# internal_excitation_2.net
KiCad netlist of a schematic drawn in EAGLE
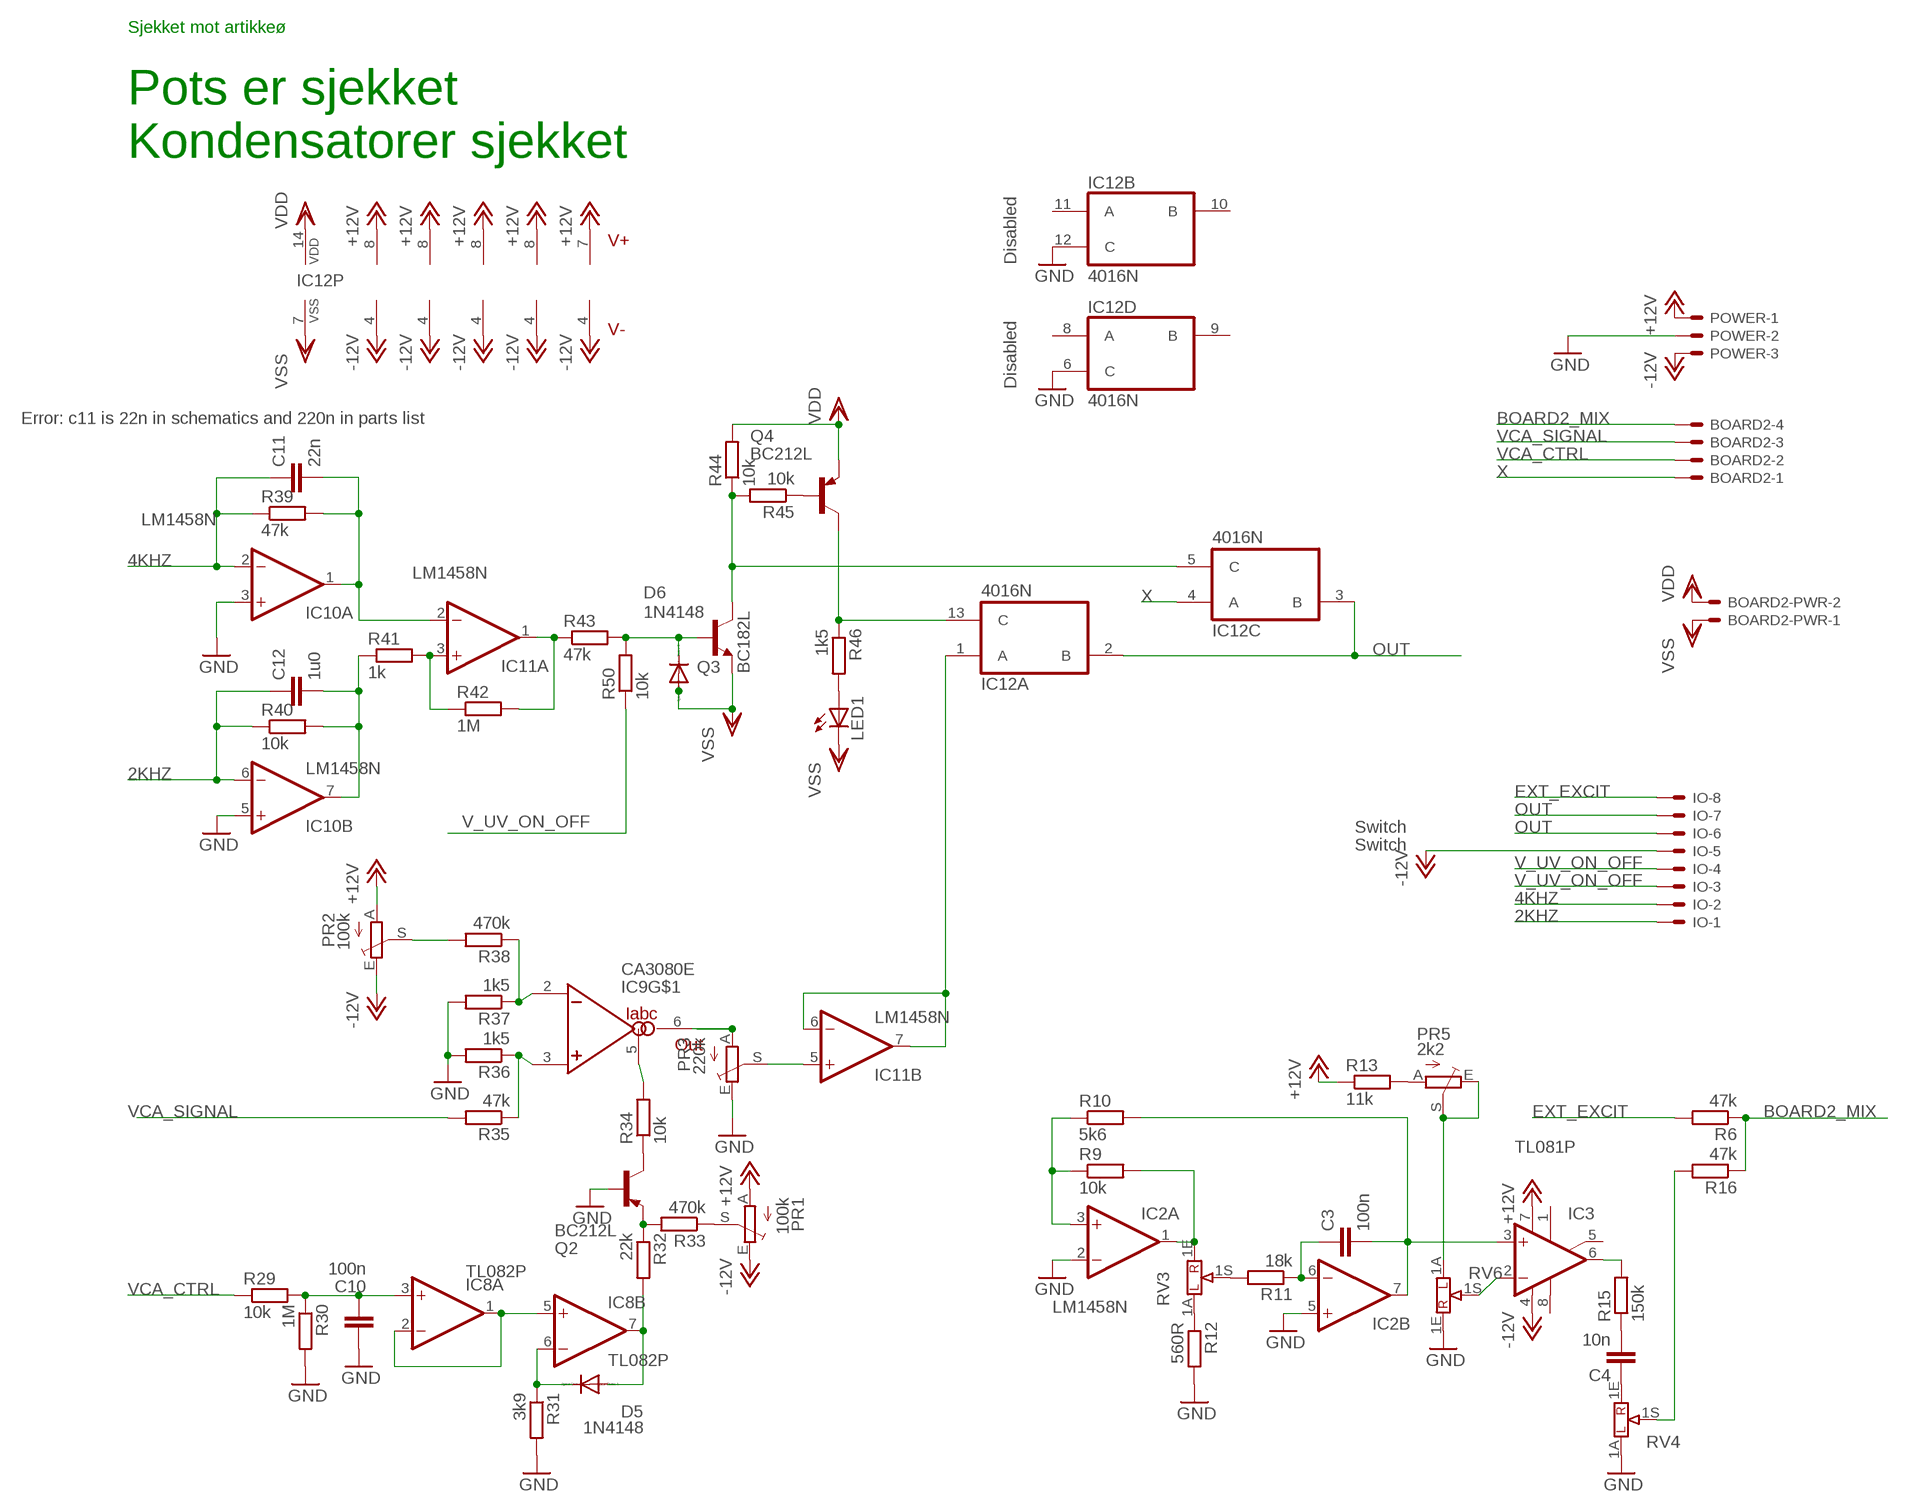
[diagram p0: schematic, sheet 1]

(export (version "E")
  (design (tool "Eeschema 10.0.6"))
  (components
    (comp (ref "BOARD2")
      (value "22-23-2041")
      (footprint "eagle-import:22-23-2041")
      (fields (field (name "MF") "MOLEX"))
      (libsource (lib "eagle-import") (part "22-23-2041"))
    )
    (comp (ref "BOARD2-PWR")
      (value "22-23-2021")
      (footprint "eagle-import:22-23-2021")
      (fields (field (name "MF") "MOLEX"))
      (libsource (lib "eagle-import") (part "22-23-2021"))
    )
    (comp (ref "C3")
      (value "100n")
      (footprint "eagle-import:C075-032X103")
      (libsource (lib "eagle-import") (part "C-EU075-032X103"))
    )
    (comp (ref "C4")
      (value "10n")
      (footprint "eagle-import:C025-025X050")
      (libsource (lib "eagle-import") (part "C-EU025-025X050"))
    )
    (comp (ref "C10")
      (value "100n")
      (footprint "eagle-import:C075-032X103")
      (libsource (lib "eagle-import") (part "C-EU075-032X103"))
    )
    (comp (ref "C11")
      (value "22n")
      (footprint "eagle-import:C050-025X075")
      (libsource (lib "eagle-import") (part "C-EU050-025X075"))
    )
    (comp (ref "C12")
      (value "1u0")
      (footprint "eagle-import:C050-025X075")
      (libsource (lib "eagle-import") (part "C-EU050-025X075"))
    )
    (comp (ref "D5")
      (value "1N4148")
      (footprint "eagle-import:DO35-5J")
      (libsource (lib "eagle-import") (part "1N4148DOJ35-5"))
    )
    (comp (ref "D6")
      (value "1N4148")
      (footprint "eagle-import:DO35-5J")
      (libsource (lib "eagle-import") (part "1N4148DOJ35-5"))
    )
    (comp (ref "IC2")
      (value "LM1458N")
      (footprint "eagle-import:DIL08")
      (libsource (lib "eagle-import") (part "1458NLM"))
    )
    (comp (ref "IC3")
      (value "TL081P")
      (footprint "eagle-import:DIL08")
      (libsource (lib "eagle-import") (part "TL081P"))
    )
    (comp (ref "IC8")
      (value "TL082P")
      (footprint "eagle-import:DIL08")
      (libsource (lib "eagle-import") (part "TL082P"))
    )
    (comp (ref "IC9")
      (value "CA3080E")
      (footprint "eagle-import:DIL08")
      (libsource (lib "eagle-import") (part "CA3080E"))
    )
    (comp (ref "IC10")
      (value "LM1458N")
      (footprint "eagle-import:DIL08")
      (libsource (lib "eagle-import") (part "1458NLM"))
    )
    (comp (ref "IC11")
      (value "LM1458N")
      (footprint "eagle-import:DIL08")
      (libsource (lib "eagle-import") (part "1458NLM"))
    )
    (comp (ref "IC12")
      (value "4016N")
      (footprint "eagle-import:DIL14")
      (libsource (lib "eagle-import") (part "4016N"))
    )
    (comp (ref "IO")
      (value "22-23-2081")
      (footprint "eagle-import:22-23-2081")
      (fields (field (name "MF") "MOLEX"))
      (libsource (lib "eagle-import") (part "22-23-2081"))
    )
    (comp (ref "LED1")
      (value "LED3MM")
      (footprint "eagle-import:LED3MM")
      (libsource (lib "eagle-import") (part "LED3MM"))
    )
    (comp (ref "POWER")
      (value "KK-156-3")
      (footprint "eagle-import:KK-156-3")
      (libsource (lib "eagle-import") (part "KK-156-3"))
    )
    (comp (ref "PR1")
      (value "100k")
      (footprint "eagle-import:CA9V")
      (libsource (lib "eagle-import") (part "TRIM_EU-CA9V"))
    )
    (comp (ref "PR2")
      (value "100k")
      (footprint "eagle-import:CA9V")
      (libsource (lib "eagle-import") (part "TRIM_EU-CA9V"))
    )
    (comp (ref "PR3")
      (value "220k")
      (footprint "eagle-import:CA9V")
      (libsource (lib "eagle-import") (part "TRIM_EU-CA9V"))
    )
    (comp (ref "PR5")
      (value "2k2")
      (footprint "eagle-import:CA9V")
      (libsource (lib "eagle-import") (part "TRIM_EU-CA9V"))
    )
    (comp (ref "Q2")
      (value "BC212L")
      (footprint "eagle-import:TO92-CBE")
      (libsource (lib "eagle-import") (part "-PNP-TO92-CBEBF493S"))
    )
    (comp (ref "Q3")
      (value "BC182L")
      (footprint "eagle-import:TO92-ECB")
      (libsource (lib "eagle-import") (part "-NPN-TO92-ECB"))
    )
    (comp (ref "Q4")
      (value "BC212L")
      (footprint "eagle-import:TO92-CBE")
      (libsource (lib "eagle-import") (part "-PNP-TO92-CBEBF493S"))
    )
    (comp (ref "R6")
      (value "47k")
      (footprint "eagle-import:0207_10")
      (libsource (lib "eagle-import") (part "R-EU_0207/10"))
    )
    (comp (ref "R9")
      (value "10k")
      (footprint "eagle-import:0207_7")
      (libsource (lib "eagle-import") (part "R-EU_0207/7"))
    )
    (comp (ref "R10")
      (value "5k6")
      (footprint "eagle-import:0207_7")
      (libsource (lib "eagle-import") (part "R-EU_0207/7"))
    )
    (comp (ref "R11")
      (value "18k")
      (footprint "eagle-import:0207_7")
      (libsource (lib "eagle-import") (part "R-EU_0207/7"))
    )
    (comp (ref "R12")
      (value "560R")
      (footprint "eagle-import:0207_7")
      (libsource (lib "eagle-import") (part "R-EU_0207/7"))
    )
    (comp (ref "R13")
      (value "11k")
      (footprint "eagle-import:0207_7")
      (libsource (lib "eagle-import") (part "R-EU_0207/7"))
    )
    (comp (ref "R15")
      (value "150k")
      (footprint "eagle-import:0207_7")
      (libsource (lib "eagle-import") (part "R-EU_0207/7"))
    )
    (comp (ref "R16")
      (value "47k")
      (footprint "eagle-import:0207_7")
      (libsource (lib "eagle-import") (part "R-EU_0207/7"))
    )
    (comp (ref "R29")
      (value "10k")
      (footprint "eagle-import:0207_7")
      (libsource (lib "eagle-import") (part "R-EU_0207/7"))
    )
    (comp (ref "R30")
      (value "1M")
      (footprint "eagle-import:0207_7")
      (libsource (lib "eagle-import") (part "R-EU_0207/7"))
    )
    (comp (ref "R31")
      (value "3k9")
      (footprint "eagle-import:0207_7")
      (libsource (lib "eagle-import") (part "R-EU_0207/7"))
    )
    (comp (ref "R32")
      (value "22k")
      (footprint "eagle-import:0207_7")
      (libsource (lib "eagle-import") (part "R-EU_0207/7"))
    )
    (comp (ref "R33")
      (value "470k")
      (footprint "eagle-import:0207_7")
      (libsource (lib "eagle-import") (part "R-EU_0207/7"))
    )
    (comp (ref "R34")
      (value "10k")
      (footprint "eagle-import:0207_7")
      (libsource (lib "eagle-import") (part "R-EU_0207/7"))
    )
    (comp (ref "R35")
      (value "47k")
      (footprint "eagle-import:0207_7")
      (libsource (lib "eagle-import") (part "R-EU_0207/7"))
    )
    (comp (ref "R36")
      (value "1k5")
      (footprint "eagle-import:0207_7")
      (libsource (lib "eagle-import") (part "R-EU_0207/7"))
    )
    (comp (ref "R37")
      (value "1k5")
      (footprint "eagle-import:0207_7")
      (libsource (lib "eagle-import") (part "R-EU_0207/7"))
    )
    (comp (ref "R38")
      (value "470k")
      (footprint "eagle-import:0207_7")
      (libsource (lib "eagle-import") (part "R-EU_0207/7"))
    )
    (comp (ref "R39")
      (value "47k")
      (footprint "eagle-import:0207_7")
      (libsource (lib "eagle-import") (part "R-EU_0207/7"))
    )
    (comp (ref "R40")
      (value "10k")
      (footprint "eagle-import:0207_7")
      (libsource (lib "eagle-import") (part "R-EU_0207/7"))
    )
    (comp (ref "R41")
      (value "1k")
      (footprint "eagle-import:0207_7")
      (libsource (lib "eagle-import") (part "R-EU_0207/7"))
    )
    (comp (ref "R42")
      (value "1M")
      (footprint "eagle-import:0207_7")
      (libsource (lib "eagle-import") (part "R-EU_0207/7"))
    )
    (comp (ref "R43")
      (value "47k")
      (footprint "eagle-import:0207_7")
      (libsource (lib "eagle-import") (part "R-EU_0207/7"))
    )
    (comp (ref "R44")
      (value "10k")
      (footprint "eagle-import:0207_7")
      (libsource (lib "eagle-import") (part "R-EU_0207/7"))
    )
    (comp (ref "R45")
      (value "10k")
      (footprint "eagle-import:0207_7")
      (libsource (lib "eagle-import") (part "R-EU_0207/7"))
    )
    (comp (ref "R46")
      (value "1k5")
      (footprint "eagle-import:0207_7")
      (libsource (lib "eagle-import") (part "R-EU_0207/7"))
    )
    (comp (ref "R50")
      (value "10k")
      (footprint "eagle-import:0207_7")
      (libsource (lib "eagle-import") (part "R-EU_0207/7"))
    )
    (comp (ref "RV3")
      (value "10k log")
      (footprint "eagle-import:POT16_W_BRACKET")
      (libsource (lib "eagle-import") (part "POT16_W_BRACKET{dblquote}{dblquote}"))
    )
    (comp (ref "RV4")
      (value "10k log")
      (footprint "eagle-import:POT16_W_BRACKET")
      (libsource (lib "eagle-import") (part "POT16_W_BRACKET{dblquote}{dblquote}"))
    )
    (comp (ref "RV6")
      (value "10k")
      (footprint "eagle-import:POT16_W_BRACKET")
      (libsource (lib "eagle-import") (part "POT16_W_BRACKET{dblquote}{dblquote}"))
    )
  )
  (nets
    (net (code "1") (name "+12V") (class "Default")
      (node (ref "IC10") (pin "8") (pinfunction "V+_8") (pintype "power_in"))
      (node (ref "IC11") (pin "8") (pinfunction "V+_8") (pintype "power_in"))
      (node (ref "IC2") (pin "8") (pinfunction "V+_8") (pintype "power_in"))
      (node (ref "IC3") (pin "7") (pinfunction "V+_7") (pintype "power_in"))
      (node (ref "IC8") (pin "8") (pinfunction "V+_8") (pintype "power_in"))
      (node (ref "IC9") (pin "7") (pinfunction "V+_7") (pintype "bidirectional"))
      (node (ref "POWER") (pin "1") (pinfunction "S_1") (pintype "passive"))
      (node (ref "PR1") (pin "A") (pinfunction "A_A") (pintype "passive"))
      (node (ref "PR2") (pin "A") (pinfunction "A_A") (pintype "passive"))
      (node (ref "R13") (pin "1") (pinfunction "1_1") (pintype "passive"))
    )
    (net (code "2") (name "-12V") (class "Default")
      (node (ref "IC10") (pin "4") (pinfunction "V-_4") (pintype "power_in"))
      (node (ref "IC11") (pin "4") (pinfunction "V-_4") (pintype "power_in"))
      (node (ref "IC2") (pin "4") (pinfunction "V-_4") (pintype "power_in"))
      (node (ref "IC3") (pin "4") (pinfunction "V-_4") (pintype "power_in"))
      (node (ref "IC8") (pin "4") (pinfunction "V-_4") (pintype "power_in"))
      (node (ref "IC9") (pin "4") (pinfunction "V-_4") (pintype "bidirectional"))
      (node (ref "IO") (pin "5") (pinfunction "S_5") (pintype "passive"))
      (node (ref "POWER") (pin "3") (pinfunction "S_3") (pintype "passive"))
      (node (ref "PR1") (pin "E") (pinfunction "E_E") (pintype "passive"))
      (node (ref "PR2") (pin "E") (pinfunction "E_E") (pintype "passive"))
    )
    (net (code "3") (name "/2KHZ") (class "Default")
      (node (ref "C12") (pin "1") (pinfunction "1_1") (pintype "passive"))
      (node (ref "IC10") (pin "6") (pinfunction "-IN_6") (pintype "input"))
      (node (ref "IO") (pin "1") (pinfunction "S_1") (pintype "passive"))
      (node (ref "R40") (pin "1") (pinfunction "1_1") (pintype "passive"))
    )
    (net (code "4") (name "/4KHZ") (class "Default")
      (node (ref "C11") (pin "1") (pinfunction "1_1") (pintype "passive"))
      (node (ref "IC10") (pin "2") (pinfunction "-IN_2") (pintype "input"))
      (node (ref "IO") (pin "2") (pinfunction "S_2") (pintype "passive"))
      (node (ref "R39") (pin "1") (pinfunction "1_1") (pintype "passive"))
    )
    (net (code "5") (name "/BOARD2_MIX") (class "Default")
      (node (ref "BOARD2") (pin "4") (pinfunction "S_4") (pintype "passive"))
      (node (ref "R16") (pin "1") (pinfunction "1_1") (pintype "passive"))
      (node (ref "R6") (pin "1") (pinfunction "1_1") (pintype "passive"))
    )
    (net (code "6") (name "/EXT_EXCIT") (class "Default")
      (node (ref "IO") (pin "8") (pinfunction "S_8") (pintype "passive"))
      (node (ref "R6") (pin "2") (pinfunction "2_2") (pintype "passive"))
    )
    (net (code "7") (name "/OUT") (class "Default")
      (node (ref "IC12") (pin "2") (pinfunction "B_2") (pintype "tri_state"))
      (node (ref "IC12") (pin "3") (pinfunction "B_3") (pintype "tri_state"))
      (node (ref "IO") (pin "6") (pinfunction "S_6") (pintype "passive"))
      (node (ref "IO") (pin "7") (pinfunction "S_7") (pintype "passive"))
    )
    (net (code "8") (name "/VCA_CTRL") (class "Default")
      (node (ref "BOARD2") (pin "2") (pinfunction "S_2") (pintype "passive"))
      (node (ref "R29") (pin "1") (pinfunction "1_1") (pintype "passive"))
    )
    (net (code "9") (name "/VCA_SIGNAL") (class "Default")
      (node (ref "BOARD2") (pin "3") (pinfunction "S_3") (pintype "passive"))
      (node (ref "R35") (pin "2") (pinfunction "2_2") (pintype "passive"))
    )
    (net (code "10") (name "/V_UV_ON_OFF") (class "Default")
      (node (ref "IO") (pin "3") (pinfunction "S_3") (pintype "passive"))
      (node (ref "IO") (pin "4") (pinfunction "S_4") (pintype "passive"))
      (node (ref "R50") (pin "1") (pinfunction "1_1") (pintype "passive"))
    )
    (net (code "11") (name "/X") (class "Default")
      (node (ref "BOARD2") (pin "1") (pinfunction "S_1") (pintype "passive"))
      (node (ref "IC12") (pin "4") (pinfunction "A_4") (pintype "tri_state"))
    )
    (net (code "12") (name "GND") (class "Default")
      (node (ref "C10") (pin "1") (pinfunction "1_1") (pintype "passive"))
      (node (ref "IC10") (pin "3") (pinfunction "+IN_3") (pintype "input"))
      (node (ref "IC10") (pin "5") (pinfunction "+IN_5") (pintype "input"))
      (node (ref "IC12") (pin "12") (pinfunction "C_12") (pintype "input"))
      (node (ref "IC12") (pin "6") (pinfunction "C_6") (pintype "input"))
      (node (ref "IC2") (pin "2") (pinfunction "-IN_2") (pintype "input"))
      (node (ref "IC2") (pin "5") (pinfunction "+IN_5") (pintype "input"))
      (node (ref "POWER") (pin "2") (pinfunction "S_2") (pintype "passive"))
      (node (ref "PR3") (pin "E") (pinfunction "E_E") (pintype "passive"))
      (node (ref "Q2") (pin "B") (pinfunction "B_B") (pintype "passive"))
      (node (ref "R12") (pin "2") (pinfunction "2_2") (pintype "passive"))
      (node (ref "R30") (pin "2") (pinfunction "2_2") (pintype "passive"))
      (node (ref "R31") (pin "2") (pinfunction "2_2") (pintype "passive"))
      (node (ref "R36") (pin "2") (pinfunction "2_2") (pintype "passive"))
      (node (ref "R37") (pin "2") (pinfunction "2_2") (pintype "passive"))
      (node (ref "RV4") (pin "1A") (pinfunction "1A_1A") (pintype "passive"))
      (node (ref "RV6") (pin "1E") (pinfunction "1E_1E") (pintype "passive"))
    )
    (net (code "13") (name "Net-(C4-Pad1)") (class "Default")
      (node (ref "C4") (pin "1") (pinfunction "1_1") (pintype "passive"))
      (node (ref "RV4") (pin "1E") (pinfunction "1E_1E") (pintype "passive"))
    )
    (net (code "14") (name "Net-(C4-Pad2)") (class "Default")
      (node (ref "C4") (pin "2") (pinfunction "2_2") (pintype "passive"))
      (node (ref "R15") (pin "1") (pinfunction "1_1") (pintype "passive"))
    )
    (net (code "15") (name "Net-(D6-PadC)") (class "Default")
      (node (ref "D6") (pin "C") (pinfunction "C_C") (pintype "passive"))
      (node (ref "Q3") (pin "B") (pinfunction "B_B") (pintype "passive"))
      (node (ref "R43") (pin "2") (pinfunction "2_2") (pintype "passive"))
      (node (ref "R50") (pin "2") (pinfunction "2_2") (pintype "passive"))
    )
    (net (code "16") (name "Net-(IC2A-+IN)") (class "Default")
      (node (ref "IC2") (pin "3") (pinfunction "+IN_3") (pintype "input"))
      (node (ref "R10") (pin "1") (pinfunction "1_1") (pintype "passive"))
      (node (ref "R9") (pin "1") (pinfunction "1_1") (pintype "passive"))
    )
    (net (code "17") (name "Net-(IC2A-OUT)") (class "Default")
      (node (ref "IC2") (pin "1") (pinfunction "OUT_1") (pintype "output"))
      (node (ref "R9") (pin "2") (pinfunction "2_2") (pintype "passive"))
      (node (ref "RV3") (pin "1E") (pinfunction "1E_1E") (pintype "passive"))
    )
    (net (code "18") (name "Net-(IC2B--IN)") (class "Default")
      (node (ref "C3") (pin "1") (pinfunction "1_1") (pintype "passive"))
      (node (ref "IC2") (pin "6") (pinfunction "-IN_6") (pintype "input"))
      (node (ref "R11") (pin "1") (pinfunction "1_1") (pintype "passive"))
    )
    (net (code "19") (name "Net-(IC2B-OUT)") (class "Default")
      (node (ref "C3") (pin "2") (pinfunction "2_2") (pintype "passive"))
      (node (ref "IC2") (pin "7") (pinfunction "OUT_7") (pintype "output"))
      (node (ref "IC3") (pin "3") (pinfunction "+IN_3") (pintype "input"))
      (node (ref "R10") (pin "2") (pinfunction "2_2") (pintype "passive"))
    )
    (net (code "20") (name "Net-(IC3--IN)") (class "Default")
      (node (ref "IC3") (pin "2") (pinfunction "-IN_2") (pintype "input"))
      (node (ref "RV6") (pin "1S") (pinfunction "1S_1S") (pintype "passive"))
    )
    (net (code "21") (name "Net-(IC3-OUT)") (class "Default")
      (node (ref "IC3") (pin "6") (pinfunction "OUT_6") (pintype "output"))
      (node (ref "R15") (pin "2") (pinfunction "2_2") (pintype "passive"))
    )
    (net (code "22") (name "Net-(IC8A-+IN)") (class "Default")
      (node (ref "C10") (pin "2") (pinfunction "2_2") (pintype "passive"))
      (node (ref "IC8") (pin "3") (pinfunction "+IN_3") (pintype "input"))
      (node (ref "R29") (pin "2") (pinfunction "2_2") (pintype "passive"))
      (node (ref "R30") (pin "1") (pinfunction "1_1") (pintype "passive"))
    )
    (net (code "23") (name "Net-(IC8A--IN)") (class "Default")
      (node (ref "IC8") (pin "1") (pinfunction "OUT_1") (pintype "output"))
      (node (ref "IC8") (pin "2") (pinfunction "-IN_2") (pintype "input"))
      (node (ref "IC8") (pin "5") (pinfunction "+IN_5") (pintype "input"))
    )
    (net (code "24") (name "Net-(IC8B--IN)") (class "Default")
      (node (ref "D5") (pin "C") (pinfunction "C_C") (pintype "passive"))
      (node (ref "IC8") (pin "6") (pinfunction "-IN_6") (pintype "input"))
      (node (ref "R31") (pin "1") (pinfunction "1_1") (pintype "passive"))
    )
    (net (code "25") (name "Net-(IC8B-OUT)") (class "Default")
      (node (ref "D5") (pin "A") (pinfunction "A_A") (pintype "passive"))
      (node (ref "IC8") (pin "7") (pinfunction "OUT_7") (pintype "output"))
      (node (ref "R32") (pin "2") (pinfunction "2_2") (pintype "passive"))
    )
    (net (code "26") (name "Net-(IC9A-+IN)") (class "Default")
      (node (ref "IC9") (pin "3") (pinfunction "+IN_3") (pintype "bidirectional"))
      (node (ref "R35") (pin "1") (pinfunction "1_1") (pintype "passive"))
      (node (ref "R36") (pin "1") (pinfunction "1_1") (pintype "passive"))
    )
    (net (code "27") (name "Net-(IC9A--IN)") (class "Default")
      (node (ref "IC9") (pin "2") (pinfunction "-IN_2") (pintype "bidirectional"))
      (node (ref "R37") (pin "1") (pinfunction "1_1") (pintype "passive"))
      (node (ref "R38") (pin "1") (pinfunction "1_1") (pintype "passive"))
    )
    (net (code "28") (name "Net-(IC9A-IABC)") (class "Default")
      (node (ref "IC9") (pin "5") (pinfunction "IABC_5") (pintype "bidirectional"))
      (node (ref "R34") (pin "2") (pinfunction "2_2") (pintype "passive"))
    )
    (net (code "29") (name "Net-(IC9A-OUT)") (class "Default")
      (node (ref "IC9") (pin "6") (pinfunction "OUT_6") (pintype "bidirectional"))
      (node (ref "PR3") (pin "A") (pinfunction "A_A") (pintype "passive"))
    )
    (net (code "30") (name "Net-(IC10A-OUT)") (class "Default")
      (node (ref "C11") (pin "2") (pinfunction "2_2") (pintype "passive"))
      (node (ref "IC10") (pin "1") (pinfunction "OUT_1") (pintype "output"))
      (node (ref "IC11") (pin "2") (pinfunction "-IN_2") (pintype "input"))
      (node (ref "R39") (pin "2") (pinfunction "2_2") (pintype "passive"))
    )
    (net (code "31") (name "Net-(IC10B-OUT)") (class "Default")
      (node (ref "C12") (pin "2") (pinfunction "2_2") (pintype "passive"))
      (node (ref "IC10") (pin "7") (pinfunction "OUT_7") (pintype "output"))
      (node (ref "R40") (pin "2") (pinfunction "2_2") (pintype "passive"))
      (node (ref "R41") (pin "1") (pinfunction "1_1") (pintype "passive"))
    )
    (net (code "32") (name "Net-(IC11A-+IN)") (class "Default")
      (node (ref "IC11") (pin "3") (pinfunction "+IN_3") (pintype "input"))
      (node (ref "R41") (pin "2") (pinfunction "2_2") (pintype "passive"))
      (node (ref "R42") (pin "1") (pinfunction "1_1") (pintype "passive"))
    )
    (net (code "33") (name "Net-(IC11A-OUT)") (class "Default")
      (node (ref "IC11") (pin "1") (pinfunction "OUT_1") (pintype "output"))
      (node (ref "R42") (pin "2") (pinfunction "2_2") (pintype "passive"))
      (node (ref "R43") (pin "1") (pinfunction "1_1") (pintype "passive"))
    )
    (net (code "34") (name "Net-(IC11B-+IN)") (class "Default")
      (node (ref "IC11") (pin "5") (pinfunction "+IN_5") (pintype "input"))
      (node (ref "PR3") (pin "S") (pinfunction "S_S") (pintype "passive"))
    )
    (net (code "35") (name "Net-(IC11B--IN)") (class "Default")
      (node (ref "IC11") (pin "6") (pinfunction "-IN_6") (pintype "input"))
      (node (ref "IC11") (pin "7") (pinfunction "OUT_7") (pintype "output"))
      (node (ref "IC12") (pin "1") (pinfunction "A_1") (pintype "tri_state"))
    )
    (net (code "36") (name "Net-(IC12A-C)") (class "Default")
      (node (ref "IC12") (pin "13") (pinfunction "C_13") (pintype "input"))
      (node (ref "Q4") (pin "C") (pinfunction "C_C") (pintype "passive"))
      (node (ref "R46") (pin "1") (pinfunction "1_1") (pintype "passive"))
    )
    (net (code "37") (name "Net-(IC12C-C)") (class "Default")
      (node (ref "IC12") (pin "5") (pinfunction "C_5") (pintype "input"))
      (node (ref "Q3") (pin "C") (pinfunction "C_C") (pintype "passive"))
      (node (ref "R44") (pin "1") (pinfunction "1_1") (pintype "passive"))
      (node (ref "R45") (pin "2") (pinfunction "2_2") (pintype "passive"))
    )
    (net (code "38") (name "Net-(LED1-PadA)") (class "Default")
      (node (ref "LED1") (pin "A") (pinfunction "A_A") (pintype "passive"))
      (node (ref "R46") (pin "2") (pinfunction "2_2") (pintype "passive"))
    )
    (net (code "39") (name "Net-(PR1-PadS)") (class "Default")
      (node (ref "PR1") (pin "S") (pinfunction "S_S") (pintype "passive"))
      (node (ref "R33") (pin "1") (pinfunction "1_1") (pintype "passive"))
    )
    (net (code "40") (name "Net-(PR2-PadS)") (class "Default")
      (node (ref "PR2") (pin "S") (pinfunction "S_S") (pintype "passive"))
      (node (ref "R38") (pin "2") (pinfunction "2_2") (pintype "passive"))
    )
    (net (code "41") (name "Net-(PR5-PadA)") (class "Default")
      (node (ref "PR5") (pin "A") (pinfunction "A_A") (pintype "passive"))
      (node (ref "R13") (pin "2") (pinfunction "2_2") (pintype "passive"))
    )
    (net (code "42") (name "Net-(PR5-PadE)") (class "Default")
      (node (ref "PR5") (pin "E") (pinfunction "E_E") (pintype "passive"))
      (node (ref "PR5") (pin "S") (pinfunction "S_S") (pintype "passive"))
      (node (ref "RV6") (pin "1A") (pinfunction "1A_1A") (pintype "passive"))
    )
    (net (code "43") (name "Net-(Q2-PadC)") (class "Default")
      (node (ref "Q2") (pin "C") (pinfunction "C_C") (pintype "passive"))
      (node (ref "R34") (pin "1") (pinfunction "1_1") (pintype "passive"))
    )
    (net (code "44") (name "Net-(Q2-PadE)") (class "Default")
      (node (ref "Q2") (pin "E") (pinfunction "E_E") (pintype "passive"))
      (node (ref "R32") (pin "1") (pinfunction "1_1") (pintype "passive"))
      (node (ref "R33") (pin "2") (pinfunction "2_2") (pintype "passive"))
    )
    (net (code "45") (name "Net-(Q4-PadB)") (class "Default")
      (node (ref "Q4") (pin "B") (pinfunction "B_B") (pintype "passive"))
      (node (ref "R45") (pin "1") (pinfunction "1_1") (pintype "passive"))
    )
    (net (code "46") (name "Net-(R11-Pad2)") (class "Default")
      (node (ref "R11") (pin "2") (pinfunction "2_2") (pintype "passive"))
      (node (ref "RV3") (pin "1S") (pinfunction "1S_1S") (pintype "passive"))
    )
    (net (code "47") (name "Net-(R12-Pad1)") (class "Default")
      (node (ref "R12") (pin "1") (pinfunction "1_1") (pintype "passive"))
      (node (ref "RV3") (pin "1A") (pinfunction "1A_1A") (pintype "passive"))
    )
    (net (code "48") (name "Net-(R16-Pad2)") (class "Default")
      (node (ref "R16") (pin "2") (pinfunction "2_2") (pintype "passive"))
      (node (ref "RV4") (pin "1S") (pinfunction "1S_1S") (pintype "passive"))
    )
    (net (code "49") (name "VDD") (class "Default")
      (node (ref "BOARD2-PWR") (pin "2") (pinfunction "S_2") (pintype "passive"))
      (node (ref "IC12") (pin "14") (pinfunction "VDD_14") (pintype "power_in"))
      (node (ref "Q4") (pin "E") (pinfunction "E_E") (pintype "passive"))
      (node (ref "R44") (pin "2") (pinfunction "2_2") (pintype "passive"))
    )
    (net (code "50") (name "VSS") (class "Default")
      (node (ref "BOARD2-PWR") (pin "1") (pinfunction "S_1") (pintype "passive"))
      (node (ref "D6") (pin "A") (pinfunction "A_A") (pintype "passive"))
      (node (ref "IC12") (pin "7") (pinfunction "VSS_7") (pintype "power_in"))
      (node (ref "LED1") (pin "K") (pinfunction "C_K") (pintype "passive"))
      (node (ref "Q3") (pin "E") (pinfunction "E_E") (pintype "passive"))
    )
    (net (code "51") (name "unconnected-(IC3-ON1-Pad1)") (class "Default")
      (node (ref "IC3") (pin "1") (pinfunction "ON1_1") (pintype "passive"))
    )
    (net (code "52") (name "unconnected-(IC3-ON2-Pad5)") (class "Default")
      (node (ref "IC3") (pin "5") (pinfunction "ON2_5") (pintype "passive"))
    )
    (net (code "53") (name "unconnected-(IC3-OPT-Pad8)") (class "Default")
      (node (ref "IC3") (pin "8") (pinfunction "OPT_8") (pintype "passive"))
    )
    (net (code "54") (name "unconnected-(IC12B-A-Pad11)") (class "Default")
      (node (ref "IC12") (pin "11") (pinfunction "A_11") (pintype "tri_state"))
    )
    (net (code "55") (name "unconnected-(IC12B-B-Pad10)") (class "Default")
      (node (ref "IC12") (pin "10") (pinfunction "B_10") (pintype "tri_state"))
    )
    (net (code "56") (name "unconnected-(IC12D-A-Pad8)") (class "Default")
      (node (ref "IC12") (pin "8") (pinfunction "A_8") (pintype "tri_state"))
    )
    (net (code "57") (name "unconnected-(IC12D-B-Pad9)") (class "Default")
      (node (ref "IC12") (pin "9") (pinfunction "B_9") (pintype "tri_state"))
    )
  )
)
